# 08_LMS1_RF.net
KiCad netlist of a schematic drawn in Altium Designer
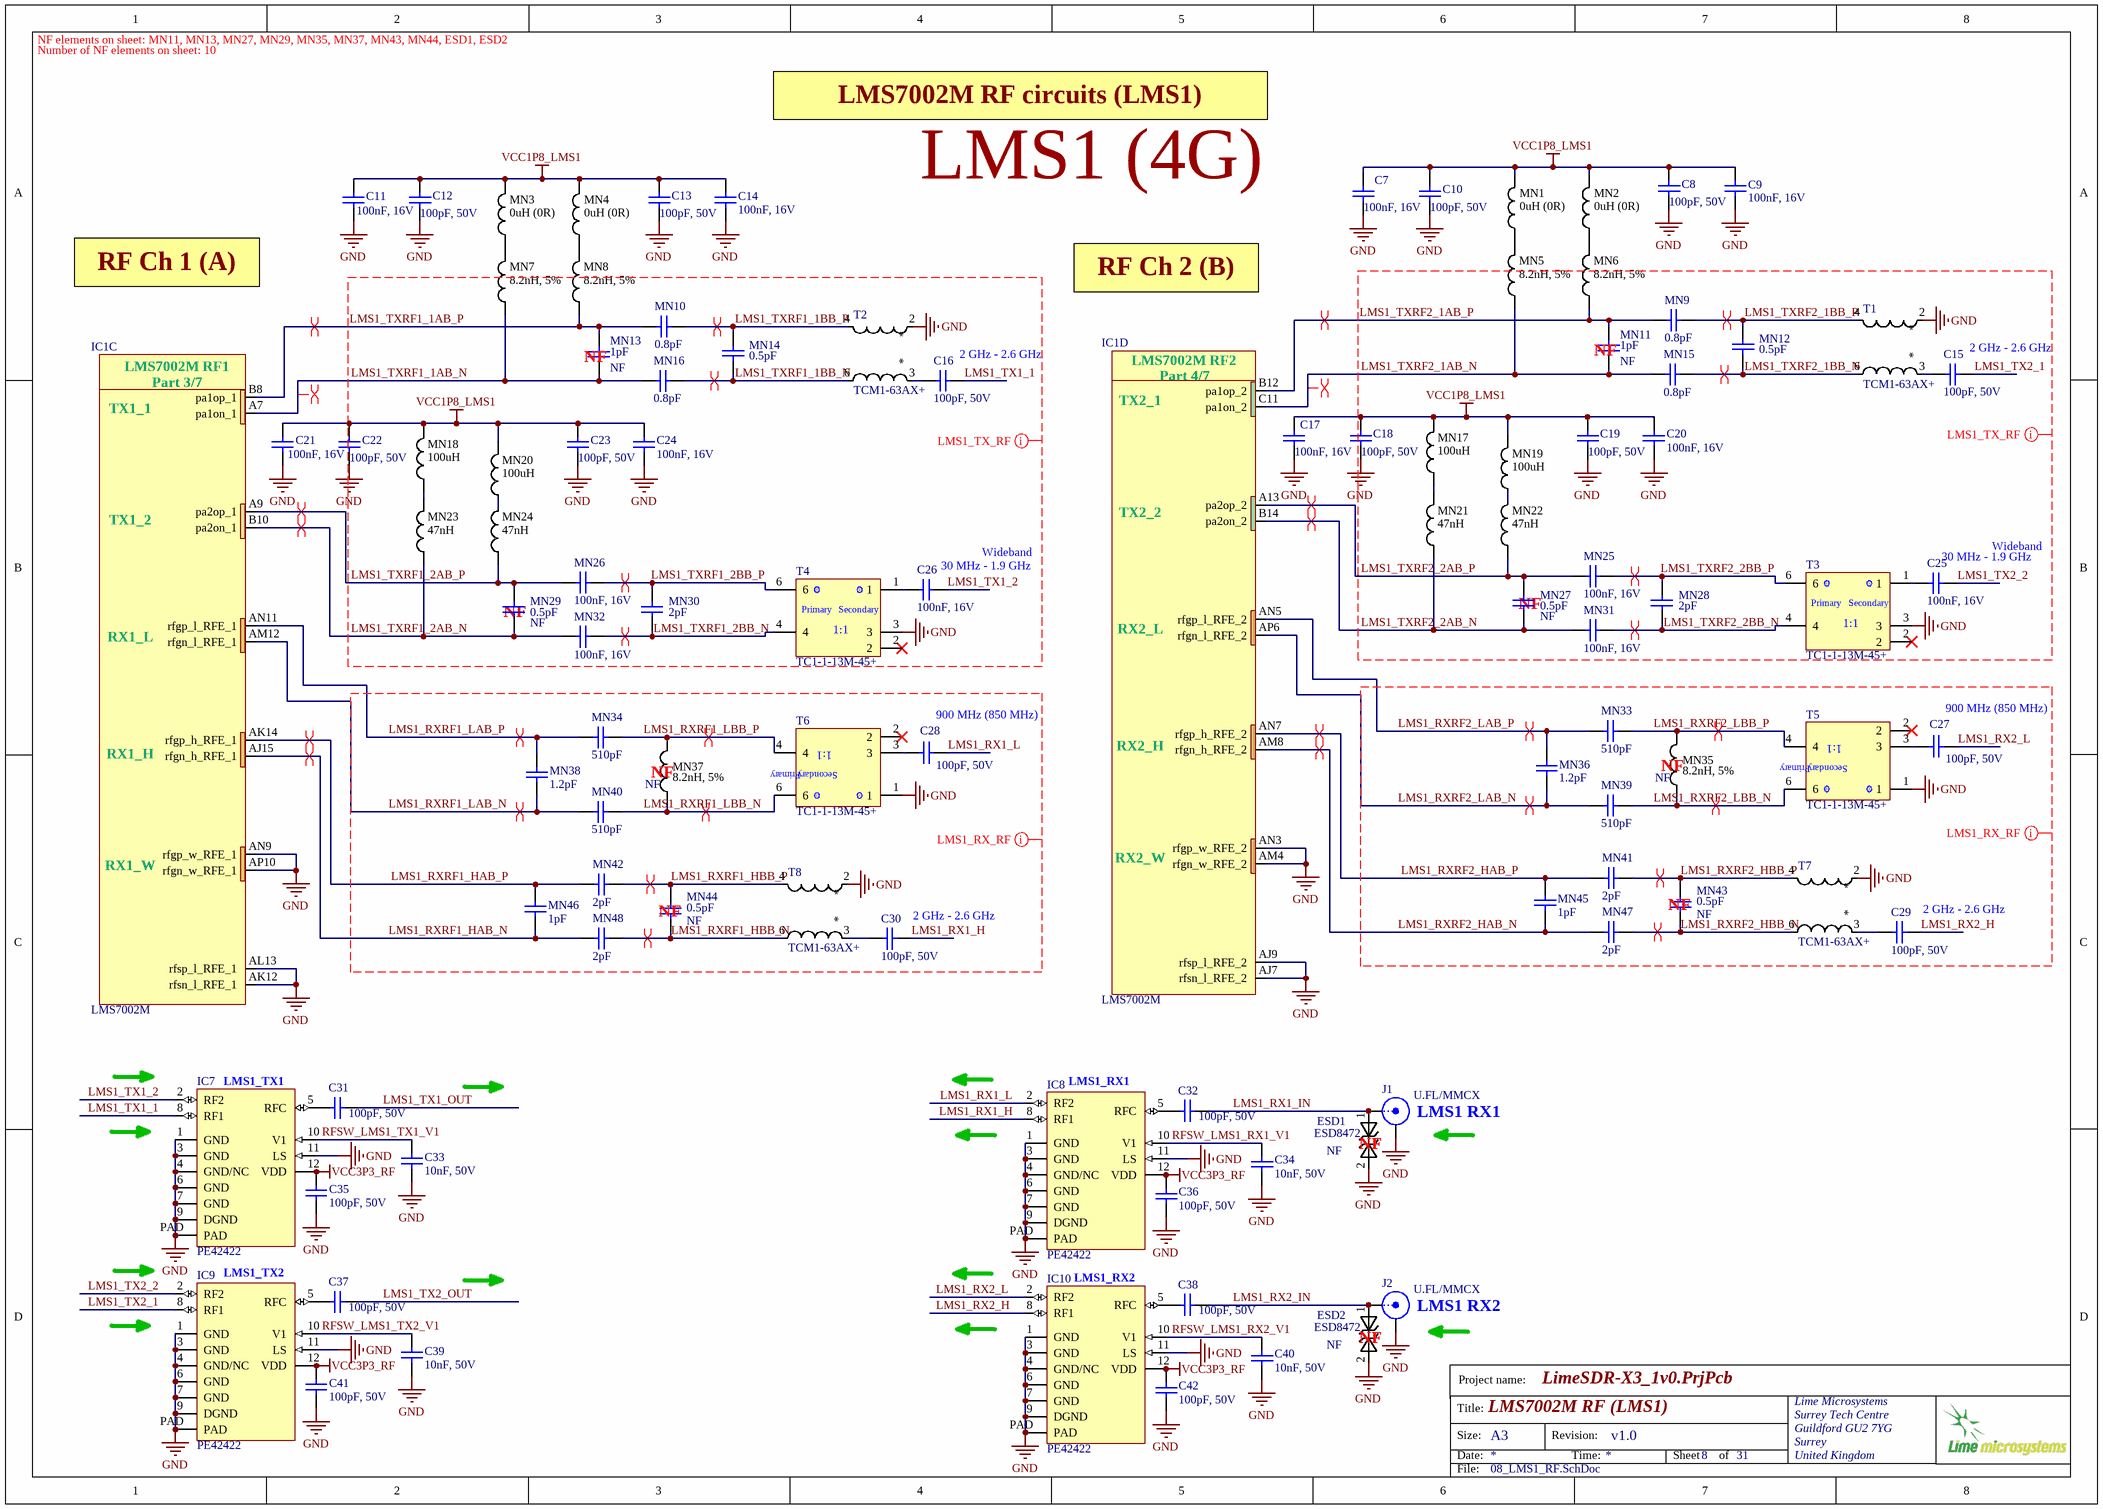
[diagram p0: 08_LMS1_RF.SchDoc]

(export (version "E")
  (design (tool "Eeschema 10.0.6"))
  (components
    (comp (ref "C7")
      (value "100nF, 16V")
      (footprint "CAP0402")
      (fields (field (name "MANUFACTURER") "Murata Electronics") (field (name "TOLERANCE") "10 %"))
      (libsource (lib "") (part "Cap_0402_4"))
    )
    (comp (ref "C8")
      (value "100pF, 50V")
      (footprint "CAP0402")
      (fields (field (name "MANUFACTURER") "Yageo") (field (name "TOLERANCE") "±5%"))
      (libsource (lib "") (part "Cap_0402_5"))
    )
    (comp (ref "C9")
      (value "100nF, 16V")
      (footprint "CAP0402")
      (fields (field (name "MANUFACTURER") "Murata Electronics") (field (name "TOLERANCE") "10 %"))
      (libsource (lib "") (part "Cap_0402_4"))
    )
    (comp (ref "C10")
      (value "100pF, 50V")
      (footprint "CAP0402")
      (fields (field (name "MANUFACTURER") "Yageo") (field (name "TOLERANCE") "±5%"))
      (libsource (lib "") (part "Cap_0402_5"))
    )
    (comp (ref "C11")
      (value "100nF, 16V")
      (footprint "CAP0402")
      (fields (field (name "MANUFACTURER") "Murata Electronics") (field (name "TOLERANCE") "10 %"))
      (libsource (lib "") (part "Cap_0402_4"))
    )
    (comp (ref "C12")
      (value "100pF, 50V")
      (footprint "CAP0402")
      (fields (field (name "MANUFACTURER") "Yageo") (field (name "TOLERANCE") "±5%"))
      (libsource (lib "") (part "Cap_0402_5"))
    )
    (comp (ref "C13")
      (value "100pF, 50V")
      (footprint "CAP0402")
      (fields (field (name "MANUFACTURER") "Yageo") (field (name "TOLERANCE") "±5%"))
      (libsource (lib "") (part "Cap_0402_5"))
    )
    (comp (ref "C14")
      (value "100nF, 16V")
      (footprint "CAP0402")
      (fields (field (name "MANUFACTURER") "Murata Electronics") (field (name "TOLERANCE") "10 %"))
      (libsource (lib "") (part "Cap_0402_4"))
    )
    (comp (ref "C15")
      (value "100pF, 50V")
      (footprint "CAP0402")
      (fields (field (name "TOLERANCE") "±5%") (field (name "MANUFACTURER") "Yageo"))
      (libsource (lib "") (part "Cap_0402_12"))
    )
    (comp (ref "C16")
      (value "100pF, 50V")
      (footprint "CAP0402")
      (fields (field (name "TOLERANCE") "±5%") (field (name "MANUFACTURER") "Yageo"))
      (libsource (lib "") (part "Cap_0402_12"))
    )
    (comp (ref "C17")
      (value "100nF, 16V")
      (footprint "CAP0402")
      (fields (field (name "MANUFACTURER") "Murata Electronics") (field (name "TOLERANCE") "10 %"))
      (libsource (lib "") (part "Cap_0402_7"))
    )
    (comp (ref "C18")
      (value "100pF, 50V")
      (footprint "CAP0402")
      (fields (field (name "MANUFACTURER") "Yageo") (field (name "TOLERANCE") "±5%"))
      (libsource (lib "") (part "Cap_0402_5"))
    )
    (comp (ref "C19")
      (value "100pF, 50V")
      (footprint "CAP0402")
      (fields (field (name "MANUFACTURER") "Yageo") (field (name "TOLERANCE") "±5%"))
      (libsource (lib "") (part "Cap_0402_5"))
    )
    (comp (ref "C20")
      (value "100nF, 16V")
      (footprint "CAP0402")
      (fields (field (name "MANUFACTURER") "Murata Electronics") (field (name "TOLERANCE") "10 %"))
      (libsource (lib "") (part "Cap_0402_7"))
    )
    (comp (ref "C21")
      (value "100nF, 16V")
      (footprint "CAP0402")
      (fields (field (name "MANUFACTURER") "Murata Electronics") (field (name "TOLERANCE") "10 %"))
      (libsource (lib "") (part "Cap_0402_7"))
    )
    (comp (ref "C22")
      (value "100pF, 50V")
      (footprint "CAP0402")
      (fields (field (name "MANUFACTURER") "Yageo") (field (name "TOLERANCE") "±5%"))
      (libsource (lib "") (part "Cap_0402_5"))
    )
    (comp (ref "C23")
      (value "100pF, 50V")
      (footprint "CAP0402")
      (fields (field (name "MANUFACTURER") "Yageo") (field (name "TOLERANCE") "±5%"))
      (libsource (lib "") (part "Cap_0402_5"))
    )
    (comp (ref "C24")
      (value "100nF, 16V")
      (footprint "CAP0402")
      (fields (field (name "MANUFACTURER") "Murata Electronics") (field (name "TOLERANCE") "10 %"))
      (libsource (lib "") (part "Cap_0402_7"))
    )
    (comp (ref "C25")
      (value "100nF, 16V")
      (footprint "CAP0402")
      (fields (field (name "MANUFACTURER") "Murata Electronics") (field (name "TOLERANCE") "10 %"))
      (libsource (lib "") (part "Cap_0402_11"))
    )
    (comp (ref "C26")
      (value "100nF, 16V")
      (footprint "CAP0402")
      (fields (field (name "MANUFACTURER") "Murata Electronics") (field (name "TOLERANCE") "10 %"))
      (libsource (lib "") (part "Cap_0402_11"))
    )
    (comp (ref "C27")
      (value "100pF, 50V")
      (footprint "CAP0402")
      (fields (field (name "TOLERANCE") "±5%") (field (name "MANUFACTURER") "Yageo"))
      (libsource (lib "") (part "Cap_0402_2"))
    )
    (comp (ref "C28")
      (value "100pF, 50V")
      (footprint "CAP0402")
      (fields (field (name "TOLERANCE") "±5%") (field (name "MANUFACTURER") "Yageo"))
      (libsource (lib "") (part "Cap_0402_2"))
    )
    (comp (ref "C29")
      (value "100pF, 50V")
      (footprint "CAP0402")
      (fields (field (name "TOLERANCE") "±5%") (field (name "MANUFACTURER") "Yageo"))
      (libsource (lib "") (part "Cap_0402_8"))
    )
    (comp (ref "C30")
      (value "100pF, 50V")
      (footprint "CAP0402")
      (fields (field (name "TOLERANCE") "±5%") (field (name "MANUFACTURER") "Yageo"))
      (libsource (lib "") (part "Cap_0402_8"))
    )
    (comp (ref "C31")
      (value "100pF, 50V")
      (footprint "CAP0402")
      (fields (field (name "TOLERANCE") "±5%") (field (name "MANUFACTURER") "Yageo"))
      (libsource (lib "") (part "Cap_0402_4"))
    )
    (comp (ref "C32")
      (value "100pF, 50V")
      (footprint "CAP0402")
      (fields (field (name "TOLERANCE") "±5%") (field (name "MANUFACTURER") "Yageo"))
      (libsource (lib "") (part "Cap_0402_10"))
    )
    (comp (ref "C33")
      (value "10nF, 50V")
      (footprint "CAP0402")
      (fields
        (field (name "MANUFACTURER") "Murata Electronics North America")
        (field (name "TOLERANCE") "±10%")
      )
      (libsource (lib "") (part "Cap_0402_4"))
    )
    (comp (ref "C34")
      (value "10nF, 50V")
      (footprint "CAP0402")
      (fields
        (field (name "MANUFACTURER") "Murata Electronics North America")
        (field (name "TOLERANCE") "±10%")
      )
      (libsource (lib "LimeMicroAltiumLib_schLib") (part "Cap_0402"))
    )
    (comp (ref "C35")
      (value "100pF, 50V")
      (footprint "CAP0402")
      (fields (field (name "TOLERANCE") "±5%") (field (name "MANUFACTURER") "Yageo"))
      (libsource (lib "") (part "Cap_0402_4"))
    )
    (comp (ref "C36")
      (value "100pF, 50V")
      (footprint "CAP0402")
      (fields (field (name "TOLERANCE") "±5%") (field (name "MANUFACTURER") "Yageo"))
      (libsource (lib "") (part "Cap_0402_3"))
    )
    (comp (ref "C37")
      (value "100pF, 50V")
      (footprint "CAP0402")
      (fields (field (name "TOLERANCE") "±5%") (field (name "MANUFACTURER") "Yageo"))
      (libsource (lib "") (part "Cap_0402_4"))
    )
    (comp (ref "C38")
      (value "100pF, 50V")
      (footprint "CAP0402")
      (fields (field (name "TOLERANCE") "±5%") (field (name "MANUFACTURER") "Yageo"))
      (libsource (lib "") (part "Cap_0402_10"))
    )
    (comp (ref "C39")
      (value "10nF, 50V")
      (footprint "CAP0402")
      (fields
        (field (name "MANUFACTURER") "Murata Electronics North America")
        (field (name "TOLERANCE") "±10%")
      )
      (libsource (lib "") (part "Cap_0402_4"))
    )
    (comp (ref "C40")
      (value "10nF, 50V")
      (footprint "CAP0402")
      (fields
        (field (name "MANUFACTURER") "Murata Electronics North America")
        (field (name "TOLERANCE") "±10%")
      )
      (libsource (lib "LimeMicroAltiumLib_schLib") (part "Cap_0402"))
    )
    (comp (ref "C41")
      (value "100pF, 50V")
      (footprint "CAP0402")
      (fields (field (name "TOLERANCE") "±5%") (field (name "MANUFACTURER") "Yageo"))
      (libsource (lib "") (part "Cap_0402_4"))
    )
    (comp (ref "C42")
      (value "100pF, 50V")
      (footprint "CAP0402")
      (fields (field (name "TOLERANCE") "±5%") (field (name "MANUFACTURER") "Yageo"))
      (libsource (lib "") (part "Cap_0402_3"))
    )
    (comp (ref "ESD1")
      (value "ESD8472")
      (footprint "ESD8472_X3DFN2")
      (fields (field (name "MANUFACTURER") "ON Semiconductor") (field (name "ASSEMBLY INFO") "NF"))
      (libsource (lib "LimeMicroAltiumLib_schLib") (part "ESD8472"))
    )
    (comp (ref "ESD2")
      (value "ESD8472")
      (footprint "ESD8472_X3DFN2")
      (fields (field (name "MANUFACTURER") "ON Semiconductor") (field (name "ASSEMBLY INFO") "NF"))
      (libsource (lib "LimeMicroAltiumLib_schLib") (part "ESD8472"))
    )
    (comp (ref "IC1")
      (value "LMS7002M")
      (footprint "LMS7002M_v5")
      (description "Schematic symbol revision 4. Default footprint - 0.31mm pad")
      (fields (field (name "MANUFACTURER") "Lime Microsystems"))
      (libsource (lib "LimeMicroAltiumLib_schLib_r04") (part "LMS7002Mr4"))
    )
    (comp (ref "IC7")
      (value "PE42422")
      (footprint "PE42422_QFN12")
      (fields (field (name "MANUFACTURER") "Peregrine Semiconductor"))
      (libsource (lib "") (part "PE42422_1"))
    )
    (comp (ref "IC8")
      (value "PE42422")
      (footprint "PE42422_QFN12")
      (fields (field (name "MANUFACTURER") "Peregrine Semiconductor"))
      (libsource (lib "LimeMicroAltiumLib_schLib") (part "PE42422"))
    )
    (comp (ref "IC9")
      (value "PE42422")
      (footprint "PE42422_QFN12")
      (fields (field (name "MANUFACTURER") "Peregrine Semiconductor"))
      (libsource (lib "") (part "PE42422_1"))
    )
    (comp (ref "IC10")
      (value "PE42422")
      (footprint "PE42422_QFN12")
      (fields (field (name "MANUFACTURER") "Peregrine Semiconductor"))
      (libsource (lib "LimeMicroAltiumLib_schLib") (part "PE42422"))
    )
    (comp (ref "J1")
      (value "U.FL/MMCX")
      (footprint "MMCX_UFL_conn_m")
      (description "CONN UMC RCPT STR 50 OHM SMD")
      (fields (field (name "MANUFACTURER") "Amphenol RF"))
      (libsource (lib "LimeMicroAltiumLib_schLib") (part "RF_IF_connector"))
    )
    (comp (ref "J2")
      (value "U.FL/MMCX")
      (footprint "MMCX_UFL_conn_m")
      (description "CONN UMC RCPT STR 50 OHM SMD")
      (fields (field (name "MANUFACTURER") "Amphenol RF"))
      (libsource (lib "LimeMicroAltiumLib_schLib") (part "RF_IF_connector"))
    )
    (comp (ref "MN1")
      (value "0uH (0R)")
      (footprint "RES0603")
      (fields
        (field (name "MANUFACTURER") "Panasonic Electronic Components")
        (field (name "MANUFACTURER PART NUMBER") "ERJ-3GEY0R00V")
        (field (name "TOLERANCE") "Jumper")
      )
      (libsource (lib "") (part "Inductor_0603_1"))
    )
    (comp (ref "MN2")
      (value "0uH (0R)")
      (footprint "RES0603")
      (fields
        (field (name "MANUFACTURER") "Panasonic Electronic Components")
        (field (name "MANUFACTURER PART NUMBER") "ERJ-3GEY0R00V")
        (field (name "TOLERANCE") "Jumper")
      )
      (libsource (lib "") (part "Inductor_0603_1"))
    )
    (comp (ref "MN3")
      (value "0uH (0R)")
      (footprint "RES0603")
      (fields
        (field (name "MANUFACTURER") "Panasonic Electronic Components")
        (field (name "MANUFACTURER PART NUMBER") "ERJ-3GEY0R00V")
        (field (name "TOLERANCE") "Jumper")
      )
      (libsource (lib "") (part "Inductor_0603_1"))
    )
    (comp (ref "MN4")
      (value "0uH (0R)")
      (footprint "RES0603")
      (fields
        (field (name "MANUFACTURER") "Panasonic Electronic Components")
        (field (name "MANUFACTURER PART NUMBER") "ERJ-3GEY0R00V")
        (field (name "TOLERANCE") "Jumper")
      )
      (libsource (lib "") (part "Inductor_0603_1"))
    )
    (comp (ref "MN5")
      (value "8.2nH, 5%")
      (footprint "RES0402")
      (fields (field (name "MANUFACTURER") "COILCRAFT"))
      (libsource (lib "LimeMicroAltiumLib_schLib") (part "Inductor_0603"))
    )
    (comp (ref "MN6")
      (value "8.2nH, 5%")
      (footprint "RES0402")
      (fields (field (name "MANUFACTURER") "COILCRAFT"))
      (libsource (lib "LimeMicroAltiumLib_schLib") (part "Inductor_0603"))
    )
    (comp (ref "MN7")
      (value "8.2nH, 5%")
      (footprint "RES0402")
      (fields (field (name "MANUFACTURER") "COILCRAFT"))
      (libsource (lib "LimeMicroAltiumLib_schLib") (part "Inductor_0603"))
    )
    (comp (ref "MN8")
      (value "8.2nH, 5%")
      (footprint "RES0402")
      (fields (field (name "MANUFACTURER") "COILCRAFT"))
      (libsource (lib "LimeMicroAltiumLib_schLib") (part "Inductor_0603"))
    )
    (comp (ref "MN9")
      (value "0.8pF")
      (footprint "CAP0402")
      (fields
        (field (name "TOLERANCE") "±0.1pF")
        (field (name "MANUFACTURER") "Murata Electronics North America")
        (field (name "MANUFACTURER PART NUMBER") "GRM1555C1HR80BA01D")
      )
      (libsource (lib "") (part "Cap_0402_1"))
    )
    (comp (ref "MN10")
      (value "0.8pF")
      (footprint "CAP0402")
      (fields
        (field (name "TOLERANCE") "±0.1pF")
        (field (name "MANUFACTURER") "Murata Electronics North America")
        (field (name "MANUFACTURER PART NUMBER") "GRM1555C1HR80BA01D")
      )
      (libsource (lib "") (part "Cap_0402_1"))
    )
    (comp (ref "MN11")
      (value "1pF")
      (footprint "CAP0402")
      (fields
        (field (name "ASSEMBLY INFO") "NF")
        (field (name "MANUFACTURER") "TDK Corporation")
        (field (name "TOLERANCE") "±0.1pF")
      )
      (libsource (lib "") (part "Cap_0402_2"))
    )
    (comp (ref "MN12")
      (value "0.5pF")
      (footprint "CAP0402")
      (fields (field (name "TOLERANCE") "±0.25pF") (field (name "MANUFACTURER") "Yageo"))
      (libsource (lib "") (part "Cap_0402_9"))
    )
    (comp (ref "MN13")
      (value "1pF")
      (footprint "CAP0402")
      (fields
        (field (name "ASSEMBLY INFO") "NF")
        (field (name "MANUFACTURER") "TDK Corporation")
        (field (name "TOLERANCE") "±0.1pF")
      )
      (libsource (lib "") (part "Cap_0402_2"))
    )
    (comp (ref "MN14")
      (value "0.5pF")
      (footprint "CAP0402")
      (fields (field (name "TOLERANCE") "±0.25pF") (field (name "MANUFACTURER") "Yageo"))
      (libsource (lib "") (part "Cap_0402_9"))
    )
    (comp (ref "MN15")
      (value "0.8pF")
      (footprint "CAP0402")
      (fields
        (field (name "TOLERANCE") "±0.1pF")
        (field (name "MANUFACTURER") "Murata Electronics North America")
        (field (name "MANUFACTURER PART NUMBER") "GRM1555C1HR80BA01D")
      )
      (libsource (lib "") (part "Cap_0402_1"))
    )
    (comp (ref "MN16")
      (value "0.8pF")
      (footprint "CAP0402")
      (fields
        (field (name "TOLERANCE") "±0.1pF")
        (field (name "MANUFACTURER") "Murata Electronics North America")
        (field (name "MANUFACTURER PART NUMBER") "GRM1555C1HR80BA01D")
      )
      (libsource (lib "") (part "Cap_0402_1"))
    )
    (comp (ref "MN17")
      (value "100uH")
      (footprint "RES0603")
      (fields
        (field (name "MANUFACTURER") "TDK Corporation")
        (field (name "MANUFACTURER PART NUMBER") "GLFR1608T101M-LR")
        (field (name "TOLERANCE") "±20%")
      )
      (libsource (lib "") (part "Inductor_0603_1"))
    )
    (comp (ref "MN18")
      (value "100uH")
      (footprint "RES0603")
      (fields
        (field (name "MANUFACTURER") "TDK Corporation")
        (field (name "MANUFACTURER PART NUMBER") "GLFR1608T101M-LR")
        (field (name "TOLERANCE") "±20%")
      )
      (libsource (lib "") (part "Inductor_0603_1"))
    )
    (comp (ref "MN19")
      (value "100uH")
      (footprint "RES0603")
      (fields
        (field (name "MANUFACTURER") "TDK Corporation")
        (field (name "MANUFACTURER PART NUMBER") "GLFR1608T101M-LR")
        (field (name "TOLERANCE") "±20%")
      )
      (libsource (lib "") (part "Inductor_0603_1"))
    )
    (comp (ref "MN20")
      (value "100uH")
      (footprint "RES0603")
      (fields
        (field (name "MANUFACTURER") "TDK Corporation")
        (field (name "MANUFACTURER PART NUMBER") "GLFR1608T101M-LR")
        (field (name "TOLERANCE") "±20%")
      )
      (libsource (lib "") (part "Inductor_0603_1"))
    )
    (comp (ref "MN21")
      (value "47nH")
      (footprint "RES0402")
      (fields (field (name "MANUFACTURER") "COILCRAFT"))
      (libsource (lib "") (part "Inductor_0603_2"))
    )
    (comp (ref "MN22")
      (value "47nH")
      (footprint "RES0402")
      (fields (field (name "MANUFACTURER") "COILCRAFT"))
      (libsource (lib "") (part "Inductor_0603_2"))
    )
    (comp (ref "MN23")
      (value "47nH")
      (footprint "RES0402")
      (fields (field (name "MANUFACTURER") "COILCRAFT"))
      (libsource (lib "") (part "Inductor_0603_2"))
    )
    (comp (ref "MN24")
      (value "47nH")
      (footprint "RES0402")
      (fields (field (name "MANUFACTURER") "COILCRAFT"))
      (libsource (lib "") (part "Inductor_0603_2"))
    )
    (comp (ref "MN25")
      (value "100nF, 16V")
      (footprint "CAP0402")
      (fields (field (name "MANUFACTURER") "Murata Electronics") (field (name "TOLERANCE") "10 %"))
      (libsource (lib "") (part "Cap_0402_5"))
    )
    (comp (ref "MN26")
      (value "100nF, 16V")
      (footprint "CAP0402")
      (fields (field (name "MANUFACTURER") "Murata Electronics") (field (name "TOLERANCE") "10 %"))
      (libsource (lib "") (part "Cap_0402_5"))
    )
    (comp (ref "MN27")
      (value "0.5pF")
      (footprint "CAP0402")
      (fields
        (field (name "ASSEMBLY INFO") "NF")
        (field (name "TOLERANCE") "±0.25pF")
        (field (name "MANUFACTURER") "Yageo")
      )
      (libsource (lib "") (part "Cap_0402_7"))
    )
    (comp (ref "MN28")
      (value "2pF")
      (footprint "CAP0402")
      (fields (field (name "MANUFACTURER PART NUMBER") "04025U2R0BAT2A") (field (name "MANUFACTURER") "AVX"))
      (libsource (lib "") (part "Cap_0402_7"))
    )
    (comp (ref "MN29")
      (value "0.5pF")
      (footprint "CAP0402")
      (fields
        (field (name "ASSEMBLY INFO") "NF")
        (field (name "TOLERANCE") "±0.25pF")
        (field (name "MANUFACTURER") "Yageo")
      )
      (libsource (lib "") (part "Cap_0402_7"))
    )
    (comp (ref "MN30")
      (value "2pF")
      (footprint "CAP0402")
      (fields (field (name "MANUFACTURER PART NUMBER") "04025U2R0BAT2A") (field (name "MANUFACTURER") "AVX"))
      (libsource (lib "") (part "Cap_0402_7"))
    )
    (comp (ref "MN31")
      (value "100nF, 16V")
      (footprint "CAP0402")
      (fields (field (name "MANUFACTURER") "Murata Electronics") (field (name "TOLERANCE") "10 %"))
      (libsource (lib "") (part "Cap_0402_9"))
    )
    (comp (ref "MN32")
      (value "100nF, 16V")
      (footprint "CAP0402")
      (fields (field (name "MANUFACTURER") "Murata Electronics") (field (name "TOLERANCE") "10 %"))
      (libsource (lib "") (part "Cap_0402_9"))
    )
    (comp (ref "MN33")
      (value "510pF")
      (footprint "CAP0402")
      (fields
        (field (name "TOLERANCE") "±5%")
        (field (name "MANUFACTURER") "Murata Electronics North America")
      )
      (libsource (lib "") (part "Cap_0402_4"))
    )
    (comp (ref "MN34")
      (value "510pF")
      (footprint "CAP0402")
      (fields
        (field (name "TOLERANCE") "±5%")
        (field (name "MANUFACTURER") "Murata Electronics North America")
      )
      (libsource (lib "") (part "Cap_0402_4"))
    )
    (comp (ref "MN35")
      (value "8.2nH, 5%")
      (footprint "RES0402")
      (fields (field (name "MANUFACTURER") "COILCRAFT") (field (name "ASSEMBLY INFO") "NF"))
      (libsource (lib "") (part "Inductor_0603_2"))
    )
    (comp (ref "MN36")
      (value "1.2pF")
      (footprint "CAP0402")
      (fields
        (field (name "MANUFACTURER") "Murata Electronics North America")
        (field (name "TOLERANCE") "±0.25pF")
      )
      (libsource (lib "") (part "Cap_0402_6"))
    )
    (comp (ref "MN37")
      (value "8.2nH, 5%")
      (footprint "RES0402")
      (fields (field (name "MANUFACTURER") "COILCRAFT") (field (name "ASSEMBLY INFO") "NF"))
      (libsource (lib "") (part "Inductor_0603_2"))
    )
    (comp (ref "MN38")
      (value "1.2pF")
      (footprint "CAP0402")
      (fields
        (field (name "MANUFACTURER") "Murata Electronics North America")
        (field (name "TOLERANCE") "±0.25pF")
      )
      (libsource (lib "") (part "Cap_0402_6"))
    )
    (comp (ref "MN39")
      (value "510pF")
      (footprint "CAP0402")
      (fields
        (field (name "TOLERANCE") "±5%")
        (field (name "MANUFACTURER") "Murata Electronics North America")
      )
      (libsource (lib "") (part "Cap_0402_4"))
    )
    (comp (ref "MN40")
      (value "510pF")
      (footprint "CAP0402")
      (fields
        (field (name "TOLERANCE") "±5%")
        (field (name "MANUFACTURER") "Murata Electronics North America")
      )
      (libsource (lib "") (part "Cap_0402_4"))
    )
    (comp (ref "MN41")
      (value "2pF")
      (footprint "CAP0402")
      (fields (field (name "MANUFACTURER PART NUMBER") "04025U2R0BAT2A") (field (name "MANUFACTURER") "AVX"))
      (libsource (lib "") (part "Cap_0402_1"))
    )
    (comp (ref "MN42")
      (value "2pF")
      (footprint "CAP0402")
      (fields (field (name "MANUFACTURER PART NUMBER") "04025U2R0BAT2A") (field (name "MANUFACTURER") "AVX"))
      (libsource (lib "") (part "Cap_0402_1"))
    )
    (comp (ref "MN43")
      (value "0.5pF")
      (footprint "CAP0402")
      (fields
        (field (name "ASSEMBLY INFO") "NF")
        (field (name "TOLERANCE") "±0.25pF")
        (field (name "MANUFACTURER") "Yageo")
      )
      (libsource (lib "") (part "Cap_0402_1"))
    )
    (comp (ref "MN44")
      (value "0.5pF")
      (footprint "CAP0402")
      (fields
        (field (name "ASSEMBLY INFO") "NF")
        (field (name "TOLERANCE") "±0.25pF")
        (field (name "MANUFACTURER") "Yageo")
      )
      (libsource (lib "") (part "Cap_0402_1"))
    )
    (comp (ref "MN45")
      (value "1pF")
      (footprint "CAP0402")
      (fields (field (name "MANUFACTURER") "TDK Corporation") (field (name "TOLERANCE") "±0.1pF"))
      (libsource (lib "") (part "Cap_0402_1"))
    )
    (comp (ref "MN46")
      (value "1pF")
      (footprint "CAP0402")
      (fields (field (name "MANUFACTURER") "TDK Corporation") (field (name "TOLERANCE") "±0.1pF"))
      (libsource (lib "") (part "Cap_0402_1"))
    )
    (comp (ref "MN47")
      (value "2pF")
      (footprint "CAP0402")
      (fields (field (name "MANUFACTURER PART NUMBER") "04025U2R0BAT2A") (field (name "MANUFACTURER") "AVX"))
      (libsource (lib "") (part "Cap_0402_1"))
    )
    (comp (ref "MN48")
      (value "2pF")
      (footprint "CAP0402")
      (fields (field (name "MANUFACTURER PART NUMBER") "04025U2R0BAT2A") (field (name "MANUFACTURER") "AVX"))
      (libsource (lib "") (part "Cap_0402_1"))
    )
    (comp (ref "T1")
      (value "TCM1-63AX+")
      (footprint "TCM1-63AX+_v2")
      (fields (field (name "MANUFACTURER") "Mini-circuits"))
      (libsource (lib "LimeMicroAltiumLib_schLib") (part "Balun_v2"))
    )
    (comp (ref "T2")
      (value "TCM1-63AX+")
      (footprint "TCM1-63AX+_v2")
      (fields (field (name "MANUFACTURER") "Mini-circuits"))
      (libsource (lib "LimeMicroAltiumLib_schLib") (part "Balun_v2"))
    )
    (comp (ref "T3")
      (value "TC1-1-13M-45+")
      (footprint "TC1-1-13MA+_JA4220-AL_")
      (fields (field (name "MANUFACTURER") "Minicircuits"))
      (libsource (lib "LimeMicroAltiumLib_schLib") (part "TC1-1-13M+"))
    )
    (comp (ref "T4")
      (value "TC1-1-13M-45+")
      (footprint "TC1-1-13MA+_JA4220-AL_")
      (fields (field (name "MANUFACTURER") "Minicircuits"))
      (libsource (lib "LimeMicroAltiumLib_schLib") (part "TC1-1-13M+"))
    )
    (comp (ref "T5")
      (value "TC1-1-13M-45+")
      (footprint "TC1-1-13MA+_JA4220-AL_")
      (fields (field (name "MANUFACTURER") "Minicircuits"))
      (libsource (lib "") (part "TC1-1-13M+_1"))
    )
    (comp (ref "T6")
      (value "TC1-1-13M-45+")
      (footprint "TC1-1-13MA+_JA4220-AL_")
      (fields (field (name "MANUFACTURER") "Minicircuits"))
      (libsource (lib "") (part "TC1-1-13M+_1"))
    )
    (comp (ref "T7")
      (value "TCM1-63AX+")
      (footprint "TCM1-63AX+_v2")
      (fields (field (name "MANUFACTURER") "Mini-circuits"))
      (libsource (lib "") (part "Balun_v2_1"))
    )
    (comp (ref "T8")
      (value "TCM1-63AX+")
      (footprint "TCM1-63AX+_v2")
      (fields (field (name "MANUFACTURER") "Mini-circuits"))
      (libsource (lib "") (part "Balun_v2_1"))
    )
  )
  (nets
    (net (code "1") (name "/LMS1_RX1_H") (class "Default")
      (node (ref "C30") (pin "1") (pinfunction "1_1") (pintype "passive"))
      (node (ref "IC8") (pin "8") (pinfunction "RF1_8") (pintype "bidirectional"))
    )
    (net (code "2") (name "/LMS1_RX1_IN") (class "Default")
      (node (ref "C32") (pin "1") (pinfunction "1_1") (pintype "passive"))
      (node (ref "ESD1") (pin "1") (pinfunction "1_1") (pintype "passive"))
      (node (ref "J1") (pin "1") (pinfunction "X_1") (pintype "passive"))
    )
    (net (code "3") (name "/LMS1_RX1_L") (class "Default")
      (node (ref "C28") (pin "1") (pinfunction "1_1") (pintype "passive"))
      (node (ref "IC8") (pin "2") (pinfunction "RF2_2") (pintype "bidirectional"))
    )
    (net (code "4") (name "/LMS1_RX2_H") (class "Default")
      (node (ref "C29") (pin "1") (pinfunction "1_1") (pintype "passive"))
      (node (ref "IC10") (pin "8") (pinfunction "RF1_8") (pintype "bidirectional"))
    )
    (net (code "5") (name "/LMS1_RX2_IN") (class "Default")
      (node (ref "C38") (pin "1") (pinfunction "1_1") (pintype "passive"))
      (node (ref "ESD2") (pin "1") (pinfunction "1_1") (pintype "passive"))
      (node (ref "J2") (pin "1") (pinfunction "X_1") (pintype "passive"))
    )
    (net (code "6") (name "/LMS1_RX2_L") (class "Default")
      (node (ref "C27") (pin "1") (pinfunction "1_1") (pintype "passive"))
      (node (ref "IC10") (pin "2") (pinfunction "RF2_2") (pintype "bidirectional"))
    )
    (net (code "7") (name "/LMS1_RXRF1_HAB_N") (class "Default")
      (node (ref "IC1") (pin "AJ15") (pinfunction "rfgn_h_RFE_1_AJ15") (pintype "passive"))
      (node (ref "MN46") (pin "1") (pinfunction "1_1") (pintype "passive"))
      (node (ref "MN48") (pin "2") (pinfunction "2_2") (pintype "passive"))
    )
    (net (code "8") (name "/LMS1_RXRF1_HAB_P") (class "Default")
      (node (ref "IC1") (pin "AK14") (pinfunction "rfgp_h_RFE_1_AK14") (pintype "passive"))
      (node (ref "MN42") (pin "2") (pinfunction "2_2") (pintype "passive"))
      (node (ref "MN46") (pin "2") (pinfunction "2_2") (pintype "passive"))
    )
    (net (code "9") (name "/LMS1_RXRF1_HBB_N") (class "Default")
      (node (ref "MN44") (pin "1") (pinfunction "1_1") (pintype "passive"))
      (node (ref "MN48") (pin "1") (pinfunction "1_1") (pintype "passive"))
      (node (ref "T8") (pin "6") (pinfunction "6_6") (pintype "passive"))
    )
    (net (code "10") (name "/LMS1_RXRF1_HBB_P") (class "Default")
      (node (ref "MN42") (pin "1") (pinfunction "1_1") (pintype "passive"))
      (node (ref "MN44") (pin "2") (pinfunction "2_2") (pintype "passive"))
      (node (ref "T8") (pin "4") (pinfunction "4_4") (pintype "passive"))
    )
    (net (code "11") (name "/LMS1_RXRF1_LAB_N") (class "Default")
      (node (ref "IC1") (pin "AM12") (pinfunction "rfgn_l_RFE_1_AM12") (pintype "passive"))
      (node (ref "MN38") (pin "1") (pinfunction "1_1") (pintype "passive"))
      (node (ref "MN40") (pin "2") (pinfunction "2_2") (pintype "passive"))
    )
    (net (code "12") (name "/LMS1_RXRF1_LAB_P") (class "Default")
      (node (ref "IC1") (pin "AN11") (pinfunction "rfgp_l_RFE_1_AN11") (pintype "passive"))
      (node (ref "MN34") (pin "2") (pinfunction "2_2") (pintype "passive"))
      (node (ref "MN38") (pin "2") (pinfunction "2_2") (pintype "passive"))
    )
    (net (code "13") (name "/LMS1_RXRF1_LBB_N") (class "Default")
      (node (ref "MN37") (pin "1") (pinfunction "1_1") (pintype "passive"))
      (node (ref "MN40") (pin "1") (pinfunction "1_1") (pintype "passive"))
      (node (ref "T6") (pin "6") (pinfunction "6_6") (pintype "passive"))
    )
    (net (code "14") (name "/LMS1_RXRF1_LBB_P") (class "Default")
      (node (ref "MN34") (pin "1") (pinfunction "1_1") (pintype "passive"))
      (node (ref "MN37") (pin "2") (pinfunction "2_2") (pintype "passive"))
      (node (ref "T6") (pin "4") (pinfunction "4_4") (pintype "passive"))
    )
    (net (code "15") (name "/LMS1_RXRF2_HAB_N") (class "Default")
      (node (ref "IC1") (pin "AM8") (pinfunction "rfgn_h_RFE_2_AM8") (pintype "passive"))
      (node (ref "MN45") (pin "1") (pinfunction "1_1") (pintype "passive"))
      (node (ref "MN47") (pin "2") (pinfunction "2_2") (pintype "passive"))
    )
    (net (code "16") (name "/LMS1_RXRF2_HAB_P") (class "Default")
      (node (ref "IC1") (pin "AN7") (pinfunction "rfgp_h_RFE_2_AN7") (pintype "passive"))
      (node (ref "MN41") (pin "2") (pinfunction "2_2") (pintype "passive"))
      (node (ref "MN45") (pin "2") (pinfunction "2_2") (pintype "passive"))
    )
    (net (code "17") (name "/LMS1_RXRF2_HBB_N") (class "Default")
      (node (ref "MN43") (pin "1") (pinfunction "1_1") (pintype "passive"))
      (node (ref "MN47") (pin "1") (pinfunction "1_1") (pintype "passive"))
      (node (ref "T7") (pin "6") (pinfunction "6_6") (pintype "passive"))
    )
    (net (code "18") (name "/LMS1_RXRF2_HBB_P") (class "Default")
      (node (ref "MN41") (pin "1") (pinfunction "1_1") (pintype "passive"))
      (node (ref "MN43") (pin "2") (pinfunction "2_2") (pintype "passive"))
      (node (ref "T7") (pin "4") (pinfunction "4_4") (pintype "passive"))
    )
    (net (code "19") (name "/LMS1_RXRF2_LAB_N") (class "Default")
      (node (ref "IC1") (pin "AP6") (pinfunction "rfgn_l_RFE_2_AP6") (pintype "passive"))
      (node (ref "MN36") (pin "1") (pinfunction "1_1") (pintype "passive"))
      (node (ref "MN39") (pin "2") (pinfunction "2_2") (pintype "passive"))
    )
    (net (code "20") (name "/LMS1_RXRF2_LAB_P") (class "Default")
      (node (ref "IC1") (pin "AN5") (pinfunction "rfgp_l_RFE_2_AN5") (pintype "passive"))
      (node (ref "MN33") (pin "2") (pinfunction "2_2") (pintype "passive"))
      (node (ref "MN36") (pin "2") (pinfunction "2_2") (pintype "passive"))
    )
    (net (code "21") (name "/LMS1_RXRF2_LBB_N") (class "Default")
      (node (ref "MN35") (pin "1") (pinfunction "1_1") (pintype "passive"))
      (node (ref "MN39") (pin "1") (pinfunction "1_1") (pintype "passive"))
      (node (ref "T5") (pin "6") (pinfunction "6_6") (pintype "passive"))
    )
    (net (code "22") (name "/LMS1_RXRF2_LBB_P") (class "Default")
      (node (ref "MN33") (pin "1") (pinfunction "1_1") (pintype "passive"))
      (node (ref "MN35") (pin "2") (pinfunction "2_2") (pintype "passive"))
      (node (ref "T5") (pin "4") (pinfunction "4_4") (pintype "passive"))
    )
    (net (code "23") (name "/LMS1_TX1_1") (class "Default")
      (node (ref "C16") (pin "1") (pinfunction "1_1") (pintype "passive"))
      (node (ref "IC7") (pin "8") (pinfunction "RF1_8") (pintype "bidirectional"))
    )
    (net (code "24") (name "/LMS1_TX1_2") (class "Default")
      (node (ref "C26") (pin "1") (pinfunction "1_1") (pintype "passive"))
      (node (ref "IC7") (pin "2") (pinfunction "RF2_2") (pintype "bidirectional"))
    )
    (net (code "25") (name "/LMS1_TX1_OUT") (class "Default")
      (node (ref "C31") (pin "1") (pinfunction "1_1") (pintype "passive"))
    )
    (net (code "26") (name "/LMS1_TX2_1") (class "Default")
      (node (ref "C15") (pin "1") (pinfunction "1_1") (pintype "passive"))
      (node (ref "IC9") (pin "8") (pinfunction "RF1_8") (pintype "bidirectional"))
    )
    (net (code "27") (name "/LMS1_TX2_2") (class "Default")
      (node (ref "C25") (pin "1") (pinfunction "1_1") (pintype "passive"))
      (node (ref "IC9") (pin "2") (pinfunction "RF2_2") (pintype "bidirectional"))
    )
    (net (code "28") (name "/LMS1_TX2_OUT") (class "Default")
      (node (ref "C37") (pin "1") (pinfunction "1_1") (pintype "passive"))
    )
    (net (code "29") (name "/LMS1_TXRF1_1AB_N") (class "Default")
      (node (ref "IC1") (pin "A7") (pinfunction "pa1on_1_A7") (pintype "passive"))
      (node (ref "MN13") (pin "2") (pinfunction "2_2") (pintype "passive"))
      (node (ref "MN16") (pin "2") (pinfunction "2_2") (pintype "passive"))
      (node (ref "MN7") (pin "1") (pinfunction "1_1") (pintype "passive"))
    )
    (net (code "30") (name "/LMS1_TXRF1_1AB_P") (class "Default")
      (node (ref "IC1") (pin "B8") (pinfunction "pa1op_1_B8") (pintype "passive"))
      (node (ref "MN10") (pin "2") (pinfunction "2_2") (pintype "passive"))
      (node (ref "MN13") (pin "1") (pinfunction "1_1") (pintype "passive"))
      (node (ref "MN8") (pin "1") (pinfunction "1_1") (pintype "passive"))
    )
    (net (code "31") (name "/LMS1_TXRF1_1BB_N") (class "Default")
      (node (ref "MN14") (pin "1") (pinfunction "1_1") (pintype "passive"))
      (node (ref "MN16") (pin "1") (pinfunction "1_1") (pintype "passive"))
      (node (ref "T2") (pin "6") (pinfunction "6_6") (pintype "passive"))
    )
    (net (code "32") (name "/LMS1_TXRF1_1BB_P") (class "Default")
      (node (ref "MN10") (pin "1") (pinfunction "1_1") (pintype "passive"))
      (node (ref "MN14") (pin "2") (pinfunction "2_2") (pintype "passive"))
      (node (ref "T2") (pin "4") (pinfunction "4_4") (pintype "passive"))
    )
    (net (code "33") (name "/LMS1_TXRF1_2AB_N") (class "Default")
      (node (ref "IC1") (pin "B10") (pinfunction "pa2on_1_B10") (pintype "passive"))
      (node (ref "MN23") (pin "1") (pinfunction "1_1") (pintype "passive"))
      (node (ref "MN29") (pin "1") (pinfunction "1_1") (pintype "passive"))
      (node (ref "MN32") (pin "1") (pinfunction "1_1") (pintype "passive"))
    )
    (net (code "34") (name "/LMS1_TXRF1_2AB_P") (class "Default")
      (node (ref "IC1") (pin "A9") (pinfunction "pa2op_1_A9") (pintype "passive"))
      (node (ref "MN24") (pin "1") (pinfunction "1_1") (pintype "passive"))
      (node (ref "MN26") (pin "2") (pinfunction "2_2") (pintype "passive"))
      (node (ref "MN29") (pin "2") (pinfunction "2_2") (pintype "passive"))
    )
    (net (code "35") (name "/LMS1_TXRF1_2BB_N") (class "Default")
      (node (ref "MN30") (pin "1") (pinfunction "1_1") (pintype "passive"))
      (node (ref "MN32") (pin "2") (pinfunction "2_2") (pintype "passive"))
      (node (ref "T4") (pin "4") (pinfunction "4_4") (pintype "passive"))
    )
    (net (code "36") (name "/LMS1_TXRF1_2BB_P") (class "Default")
      (node (ref "MN26") (pin "1") (pinfunction "1_1") (pintype "passive"))
      (node (ref "MN30") (pin "2") (pinfunction "2_2") (pintype "passive"))
      (node (ref "T4") (pin "6") (pinfunction "6_6") (pintype "passive"))
    )
    (net (code "37") (name "/LMS1_TXRF2_1AB_N") (class "Default")
      (node (ref "IC1") (pin "C11") (pinfunction "pa1on_2_C11") (pintype "passive"))
      (node (ref "MN11") (pin "2") (pinfunction "2_2") (pintype "passive"))
      (node (ref "MN15") (pin "2") (pinfunction "2_2") (pintype "passive"))
      (node (ref "MN5") (pin "1") (pinfunction "1_1") (pintype "passive"))
    )
    (net (code "38") (name "/LMS1_TXRF2_1AB_P") (class "Default")
      (node (ref "IC1") (pin "B12") (pinfunction "pa1op_2_B12") (pintype "passive"))
      (node (ref "MN11") (pin "1") (pinfunction "1_1") (pintype "passive"))
      (node (ref "MN6") (pin "1") (pinfunction "1_1") (pintype "passive"))
      (node (ref "MN9") (pin "2") (pinfunction "2_2") (pintype "passive"))
    )
    (net (code "39") (name "/LMS1_TXRF2_1BB_N") (class "Default")
      (node (ref "MN12") (pin "1") (pinfunction "1_1") (pintype "passive"))
      (node (ref "MN15") (pin "1") (pinfunction "1_1") (pintype "passive"))
      (node (ref "T1") (pin "6") (pinfunction "6_6") (pintype "passive"))
    )
    (net (code "40") (name "/LMS1_TXRF2_1BB_P") (class "Default")
      (node (ref "MN12") (pin "2") (pinfunction "2_2") (pintype "passive"))
      (node (ref "MN9") (pin "1") (pinfunction "1_1") (pintype "passive"))
      (node (ref "T1") (pin "4") (pinfunction "4_4") (pintype "passive"))
    )
    (net (code "41") (name "/LMS1_TXRF2_2AB_N") (class "Default")
      (node (ref "IC1") (pin "B14") (pinfunction "pa2on_2_B14") (pintype "passive"))
      (node (ref "MN21") (pin "1") (pinfunction "1_1") (pintype "passive"))
      (node (ref "MN27") (pin "1") (pinfunction "1_1") (pintype "passive"))
      (node (ref "MN31") (pin "1") (pinfunction "1_1") (pintype "passive"))
    )
    (net (code "42") (name "/LMS1_TXRF2_2AB_P") (class "Default")
      (node (ref "IC1") (pin "A13") (pinfunction "pa2op_2_A13") (pintype "passive"))
      (node (ref "MN22") (pin "1") (pinfunction "1_1") (pintype "passive"))
      (node (ref "MN25") (pin "2") (pinfunction "2_2") (pintype "passive"))
      (node (ref "MN27") (pin "2") (pinfunction "2_2") (pintype "passive"))
    )
    (net (code "43") (name "/LMS1_TXRF2_2BB_N") (class "Default")
      (node (ref "MN28") (pin "1") (pinfunction "1_1") (pintype "passive"))
      (node (ref "MN31") (pin "2") (pinfunction "2_2") (pintype "passive"))
      (node (ref "T3") (pin "4") (pinfunction "4_4") (pintype "passive"))
    )
    (net (code "44") (name "/LMS1_TXRF2_2BB_P") (class "Default")
      (node (ref "MN25") (pin "1") (pinfunction "1_1") (pintype "passive"))
      (node (ref "MN28") (pin "2") (pinfunction "2_2") (pintype "passive"))
      (node (ref "T3") (pin "6") (pinfunction "6_6") (pintype "passive"))
    )
    (net (code "45") (name "/RFSW_LMS1_RX1_V1") (class "Default")
      (node (ref "C34") (pin "1") (pinfunction "1_1") (pintype "passive"))
      (node (ref "IC8") (pin "10") (pinfunction "V1_10") (pintype "input"))
    )
    (net (code "46") (name "/RFSW_LMS1_RX2_V1") (class "Default")
      (node (ref "C40") (pin "1") (pinfunction "1_1") (pintype "passive"))
      (node (ref "IC10") (pin "10") (pinfunction "V1_10") (pintype "input"))
    )
    (net (code "47") (name "/RFSW_LMS1_TX1_V1") (class "Default")
      (node (ref "C33") (pin "1") (pinfunction "1_1") (pintype "passive"))
      (node (ref "IC7") (pin "10") (pinfunction "V1_10") (pintype "input"))
    )
    (net (code "48") (name "/RFSW_LMS1_TX2_V1") (class "Default")
      (node (ref "C39") (pin "1") (pinfunction "1_1") (pintype "passive"))
      (node (ref "IC9") (pin "10") (pinfunction "V1_10") (pintype "input"))
    )
    (net (code "49") (name "GND") (class "Default")
      (node (ref "C10") (pin "1") (pinfunction "1_1") (pintype "passive"))
      (node (ref "C11") (pin "1") (pinfunction "1_1") (pintype "passive"))
      (node (ref "C12") (pin "1") (pinfunction "1_1") (pintype "passive"))
      (node (ref "C13") (pin "1") (pinfunction "1_1") (pintype "passive"))
      (node (ref "C14") (pin "1") (pinfunction "1_1") (pintype "passive"))
      (node (ref "C17") (pin "1") (pinfunction "1_1") (pintype "passive"))
      (node (ref "C18") (pin "1") (pinfunction "1_1") (pintype "passive"))
      (node (ref "C19") (pin "1") (pinfunction "1_1") (pintype "passive"))
      (node (ref "C20") (pin "1") (pinfunction "1_1") (pintype "passive"))
      (node (ref "C21") (pin "1") (pinfunction "1_1") (pintype "passive"))
      (node (ref "C22") (pin "1") (pinfunction "1_1") (pintype "passive"))
      (node (ref "C23") (pin "1") (pinfunction "1_1") (pintype "passive"))
      (node (ref "C24") (pin "1") (pinfunction "1_1") (pintype "passive"))
      (node (ref "C33") (pin "2") (pinfunction "2_2") (pintype "passive"))
      (node (ref "C34") (pin "2") (pinfunction "2_2") (pintype "passive"))
      (node (ref "C35") (pin "1") (pinfunction "1_1") (pintype "passive"))
      (node (ref "C36") (pin "1") (pinfunction "1_1") (pintype "passive"))
      (node (ref "C39") (pin "2") (pinfunction "2_2") (pintype "passive"))
      (node (ref "C40") (pin "2") (pinfunction "2_2") (pintype "passive"))
      (node (ref "C41") (pin "1") (pinfunction "1_1") (pintype "passive"))
      (node (ref "C42") (pin "1") (pinfunction "1_1") (pintype "passive"))
      (node (ref "C7") (pin "1") (pinfunction "1_1") (pintype "passive"))
      (node (ref "C8") (pin "1") (pinfunction "1_1") (pintype "passive"))
      (node (ref "C9") (pin "1") (pinfunction "1_1") (pintype "passive"))
      (node (ref "ESD1") (pin "2") (pinfunction "2_2") (pintype "passive"))
      (node (ref "ESD2") (pin "2") (pinfunction "2_2") (pintype "passive"))
      (node (ref "IC1") (pin "AJ7") (pinfunction "rfsn_l_RFE_2_AJ7") (pintype "passive"))
      (node (ref "IC1") (pin "AJ9") (pinfunction "rfsp_l_RFE_2_AJ9") (pintype "passive"))
      (node (ref "IC1") (pin "AK12") (pinfunction "rfsn_l_RFE_1_AK12") (pintype "passive"))
      (node (ref "IC1") (pin "AL13") (pinfunction "rfsp_l_RFE_1_AL13") (pintype "passive"))
      (node (ref "IC1") (pin "AM4") (pinfunction "rfgn_w_RFE_2_AM4") (pintype "passive"))
      (node (ref "IC1") (pin "AN3") (pinfunction "rfgp_w_RFE_2_AN3") (pintype "passive"))
      (node (ref "IC1") (pin "AN9") (pinfunction "rfgp_w_RFE_1_AN9") (pintype "passive"))
      (node (ref "IC1") (pin "AP10") (pinfunction "rfgn_w_RFE_1_AP10") (pintype "passive"))
      (node (ref "IC10") (pin "1") (pinfunction "GND_1") (pintype "passive"))
      (node (ref "IC10") (pin "11") (pinfunction "LS_11") (pintype "input"))
      (node (ref "IC10") (pin "3") (pinfunction "GND_3") (pintype "passive"))
      (node (ref "IC10") (pin "4") (pinfunction "GND/NC_4") (pintype "passive"))
      (node (ref "IC10") (pin "6") (pinfunction "GND_6") (pintype "passive"))
      (node (ref "IC10") (pin "7") (pinfunction "GND_7") (pintype "passive"))
      (node (ref "IC10") (pin "9") (pinfunction "DGND_9") (pintype "passive"))
      (node (ref "IC10") (pin "PAD") (pinfunction "PAD_PAD") (pintype "passive"))
      (node (ref "IC7") (pin "1") (pinfunction "GND_1") (pintype "passive"))
      (node (ref "IC7") (pin "11") (pinfunction "LS_11") (pintype "input"))
      (node (ref "IC7") (pin "3") (pinfunction "GND_3") (pintype "passive"))
      (node (ref "IC7") (pin "4") (pinfunction "GND/NC_4") (pintype "passive"))
      (node (ref "IC7") (pin "6") (pinfunction "GND_6") (pintype "passive"))
      (node (ref "IC7") (pin "7") (pinfunction "GND_7") (pintype "passive"))
      (node (ref "IC7") (pin "9") (pinfunction "DGND_9") (pintype "passive"))
      (node (ref "IC7") (pin "PAD") (pinfunction "PAD_PAD") (pintype "passive"))
      (node (ref "IC8") (pin "1") (pinfunction "GND_1") (pintype "passive"))
      (node (ref "IC8") (pin "11") (pinfunction "LS_11") (pintype "input"))
      (node (ref "IC8") (pin "3") (pinfunction "GND_3") (pintype "passive"))
      (node (ref "IC8") (pin "4") (pinfunction "GND/NC_4") (pintype "passive"))
      (node (ref "IC8") (pin "6") (pinfunction "GND_6") (pintype "passive"))
      (node (ref "IC8") (pin "7") (pinfunction "GND_7") (pintype "passive"))
      (node (ref "IC8") (pin "9") (pinfunction "DGND_9") (pintype "passive"))
      (node (ref "IC8") (pin "PAD") (pinfunction "PAD_PAD") (pintype "passive"))
      (node (ref "IC9") (pin "1") (pinfunction "GND_1") (pintype "passive"))
      (node (ref "IC9") (pin "11") (pinfunction "LS_11") (pintype "input"))
      (node (ref "IC9") (pin "3") (pinfunction "GND_3") (pintype "passive"))
      (node (ref "IC9") (pin "4") (pinfunction "GND/NC_4") (pintype "passive"))
      (node (ref "IC9") (pin "6") (pinfunction "GND_6") (pintype "passive"))
      (node (ref "IC9") (pin "7") (pinfunction "GND_7") (pintype "passive"))
      (node (ref "IC9") (pin "9") (pinfunction "DGND_9") (pintype "passive"))
      (node (ref "IC9") (pin "PAD") (pinfunction "PAD_PAD") (pintype "passive"))
      (node (ref "J1") (pin "2") (pinfunction "Y_2") (pintype "passive"))
      (node (ref "J2") (pin "2") (pinfunction "Y_2") (pintype "passive"))
      (node (ref "T1") (pin "2") (pinfunction "2_2") (pintype "passive"))
      (node (ref "T2") (pin "2") (pinfunction "2_2") (pintype "passive"))
      (node (ref "T3") (pin "3") (pinfunction "3_3") (pintype "passive"))
      (node (ref "T4") (pin "3") (pinfunction "3_3") (pintype "passive"))
      (node (ref "T5") (pin "1") (pinfunction "1_1") (pintype "passive"))
      (node (ref "T6") (pin "1") (pinfunction "1_1") (pintype "passive"))
      (node (ref "T7") (pin "2") (pinfunction "2_2") (pintype "passive"))
      (node (ref "T8") (pin "2") (pinfunction "2_2") (pintype "passive"))
    )
    (net (code "50") (name "Net-(C15-Pad2)") (class "Default")
      (node (ref "C15") (pin "2") (pinfunction "2_2") (pintype "passive"))
      (node (ref "T1") (pin "3") (pinfunction "3_3") (pintype "passive"))
    )
    (net (code "51") (name "Net-(C16-Pad2)") (class "Default")
      (node (ref "C16") (pin "2") (pinfunction "2_2") (pintype "passive"))
      (node (ref "T2") (pin "3") (pinfunction "3_3") (pintype "passive"))
    )
    (net (code "52") (name "Net-(C25-Pad2)") (class "Default")
      (node (ref "C25") (pin "2") (pinfunction "2_2") (pintype "passive"))
      (node (ref "T3") (pin "1") (pinfunction "1_1") (pintype "passive"))
    )
    (net (code "53") (name "Net-(C26-Pad2)") (class "Default")
      (node (ref "C26") (pin "2") (pinfunction "2_2") (pintype "passive"))
      (node (ref "T4") (pin "1") (pinfunction "1_1") (pintype "passive"))
    )
    (net (code "54") (name "Net-(C27-Pad2)") (class "Default")
      (node (ref "C27") (pin "2") (pinfunction "2_2") (pintype "passive"))
      (node (ref "T5") (pin "3") (pinfunction "3_3") (pintype "passive"))
    )
    (net (code "55") (name "Net-(C28-Pad2)") (class "Default")
      (node (ref "C28") (pin "2") (pinfunction "2_2") (pintype "passive"))
      (node (ref "T6") (pin "3") (pinfunction "3_3") (pintype "passive"))
    )
    (net (code "56") (name "Net-(C29-Pad2)") (class "Default")
      (node (ref "C29") (pin "2") (pinfunction "2_2") (pintype "passive"))
      (node (ref "T7") (pin "3") (pinfunction "3_3") (pintype "passive"))
    )
    (net (code "57") (name "Net-(C30-Pad2)") (class "Default")
      (node (ref "C30") (pin "2") (pinfunction "2_2") (pintype "passive"))
      (node (ref "T8") (pin "3") (pinfunction "3_3") (pintype "passive"))
    )
    (net (code "58") (name "Net-(IC7-RFC)") (class "Default")
      (node (ref "C31") (pin "2") (pinfunction "2_2") (pintype "passive"))
      (node (ref "IC7") (pin "5") (pinfunction "RFC_5") (pintype "bidirectional"))
    )
    (net (code "59") (name "Net-(IC8-RFC)") (class "Default")
      (node (ref "C32") (pin "2") (pinfunction "2_2") (pintype "passive"))
      (node (ref "IC8") (pin "5") (pinfunction "RFC_5") (pintype "bidirectional"))
    )
    (net (code "60") (name "Net-(IC9-RFC)") (class "Default")
      (node (ref "C37") (pin "2") (pinfunction "2_2") (pintype "passive"))
      (node (ref "IC9") (pin "5") (pinfunction "RFC_5") (pintype "bidirectional"))
    )
    (net (code "61") (name "Net-(IC10-RFC)") (class "Default")
      (node (ref "C38") (pin "2") (pinfunction "2_2") (pintype "passive"))
      (node (ref "IC10") (pin "5") (pinfunction "RFC_5") (pintype "bidirectional"))
    )
    (net (code "62") (name "Net-(MN1-Pad1)") (class "Default")
      (node (ref "MN1") (pin "1") (pinfunction "1_1") (pintype "passive"))
      (node (ref "MN5") (pin "2") (pinfunction "2_2") (pintype "passive"))
    )
    (net (code "63") (name "Net-(MN2-Pad1)") (class "Default")
      (node (ref "MN2") (pin "1") (pinfunction "1_1") (pintype "passive"))
      (node (ref "MN6") (pin "2") (pinfunction "2_2") (pintype "passive"))
    )
    (net (code "64") (name "Net-(MN3-Pad1)") (class "Default")
      (node (ref "MN3") (pin "1") (pinfunction "1_1") (pintype "passive"))
      (node (ref "MN7") (pin "2") (pinfunction "2_2") (pintype "passive"))
    )
    (net (code "65") (name "Net-(MN4-Pad1)") (class "Default")
      (node (ref "MN4") (pin "1") (pinfunction "1_1") (pintype "passive"))
      (node (ref "MN8") (pin "2") (pinfunction "2_2") (pintype "passive"))
    )
    (net (code "66") (name "Net-(MN17-Pad1)") (class "Default")
      (node (ref "MN17") (pin "1") (pinfunction "1_1") (pintype "passive"))
      (node (ref "MN21") (pin "2") (pinfunction "2_2") (pintype "passive"))
    )
    (net (code "67") (name "Net-(MN18-Pad1)") (class "Default")
      (node (ref "MN18") (pin "1") (pinfunction "1_1") (pintype "passive"))
      (node (ref "MN23") (pin "2") (pinfunction "2_2") (pintype "passive"))
    )
    (net (code "68") (name "Net-(MN19-Pad1)") (class "Default")
      (node (ref "MN19") (pin "1") (pinfunction "1_1") (pintype "passive"))
      (node (ref "MN22") (pin "2") (pinfunction "2_2") (pintype "passive"))
    )
    (net (code "69") (name "Net-(MN20-Pad1)") (class "Default")
      (node (ref "MN20") (pin "1") (pinfunction "1_1") (pintype "passive"))
      (node (ref "MN24") (pin "2") (pinfunction "2_2") (pintype "passive"))
    )
    (net (code "70") (name "VCC1P8_LMS1") (class "Default")
      (node (ref "C10") (pin "2") (pinfunction "2_2") (pintype "passive"))
      (node (ref "C11") (pin "2") (pinfunction "2_2") (pintype "passive"))
      (node (ref "C12") (pin "2") (pinfunction "2_2") (pintype "passive"))
      (node (ref "C13") (pin "2") (pinfunction "2_2") (pintype "passive"))
      (node (ref "C14") (pin "2") (pinfunction "2_2") (pintype "passive"))
      (node (ref "C17") (pin "2") (pinfunction "2_2") (pintype "passive"))
      (node (ref "C18") (pin "2") (pinfunction "2_2") (pintype "passive"))
      (node (ref "C19") (pin "2") (pinfunction "2_2") (pintype "passive"))
      (node (ref "C20") (pin "2") (pinfunction "2_2") (pintype "passive"))
      (node (ref "C21") (pin "2") (pinfunction "2_2") (pintype "passive"))
      (node (ref "C22") (pin "2") (pinfunction "2_2") (pintype "passive"))
      (node (ref "C23") (pin "2") (pinfunction "2_2") (pintype "passive"))
      (node (ref "C24") (pin "2") (pinfunction "2_2") (pintype "passive"))
      (node (ref "C7") (pin "2") (pinfunction "2_2") (pintype "passive"))
      (node (ref "C8") (pin "2") (pinfunction "2_2") (pintype "passive"))
      (node (ref "C9") (pin "2") (pinfunction "2_2") (pintype "passive"))
      (node (ref "MN1") (pin "2") (pinfunction "2_2") (pintype "passive"))
      (node (ref "MN17") (pin "2") (pinfunction "2_2") (pintype "passive"))
      (node (ref "MN18") (pin "2") (pinfunction "2_2") (pintype "passive"))
      (node (ref "MN19") (pin "2") (pinfunction "2_2") (pintype "passive"))
      (node (ref "MN2") (pin "2") (pinfunction "2_2") (pintype "passive"))
      (node (ref "MN20") (pin "2") (pinfunction "2_2") (pintype "passive"))
      (node (ref "MN3") (pin "2") (pinfunction "2_2") (pintype "passive"))
      (node (ref "MN4") (pin "2") (pinfunction "2_2") (pintype "passive"))
    )
    (net (code "71") (name "VCC3P3_RF") (class "Default")
      (node (ref "C35") (pin "2") (pinfunction "2_2") (pintype "passive"))
      (node (ref "C36") (pin "2") (pinfunction "2_2") (pintype "passive"))
      (node (ref "C41") (pin "2") (pinfunction "2_2") (pintype "passive"))
      (node (ref "C42") (pin "2") (pinfunction "2_2") (pintype "passive"))
      (node (ref "IC10") (pin "12") (pinfunction "VDD_12") (pintype "power_in"))
      (node (ref "IC7") (pin "12") (pinfunction "VDD_12") (pintype "power_in"))
      (node (ref "IC8") (pin "12") (pinfunction "VDD_12") (pintype "power_in"))
      (node (ref "IC9") (pin "12") (pinfunction "VDD_12") (pintype "power_in"))
    )
    (net (code "72") (name "unconnected-(T3-Pad2)") (class "Default")
      (node (ref "T3") (pin "2") (pinfunction "2_2") (pintype "passive+no_connect"))
    )
    (net (code "73") (name "unconnected-(T4-Pad2)") (class "Default")
      (node (ref "T4") (pin "2") (pinfunction "2_2") (pintype "passive+no_connect"))
    )
    (net (code "74") (name "unconnected-(T5-Pad2)") (class "Default")
      (node (ref "T5") (pin "2") (pinfunction "2_2") (pintype "passive+no_connect"))
    )
    (net (code "75") (name "unconnected-(T6-Pad2)") (class "Default")
      (node (ref "T6") (pin "2") (pinfunction "2_2") (pintype "passive+no_connect"))
    )
  )
)
